# pad.net
KiCad netlist of a schematic drawn in EAGLE
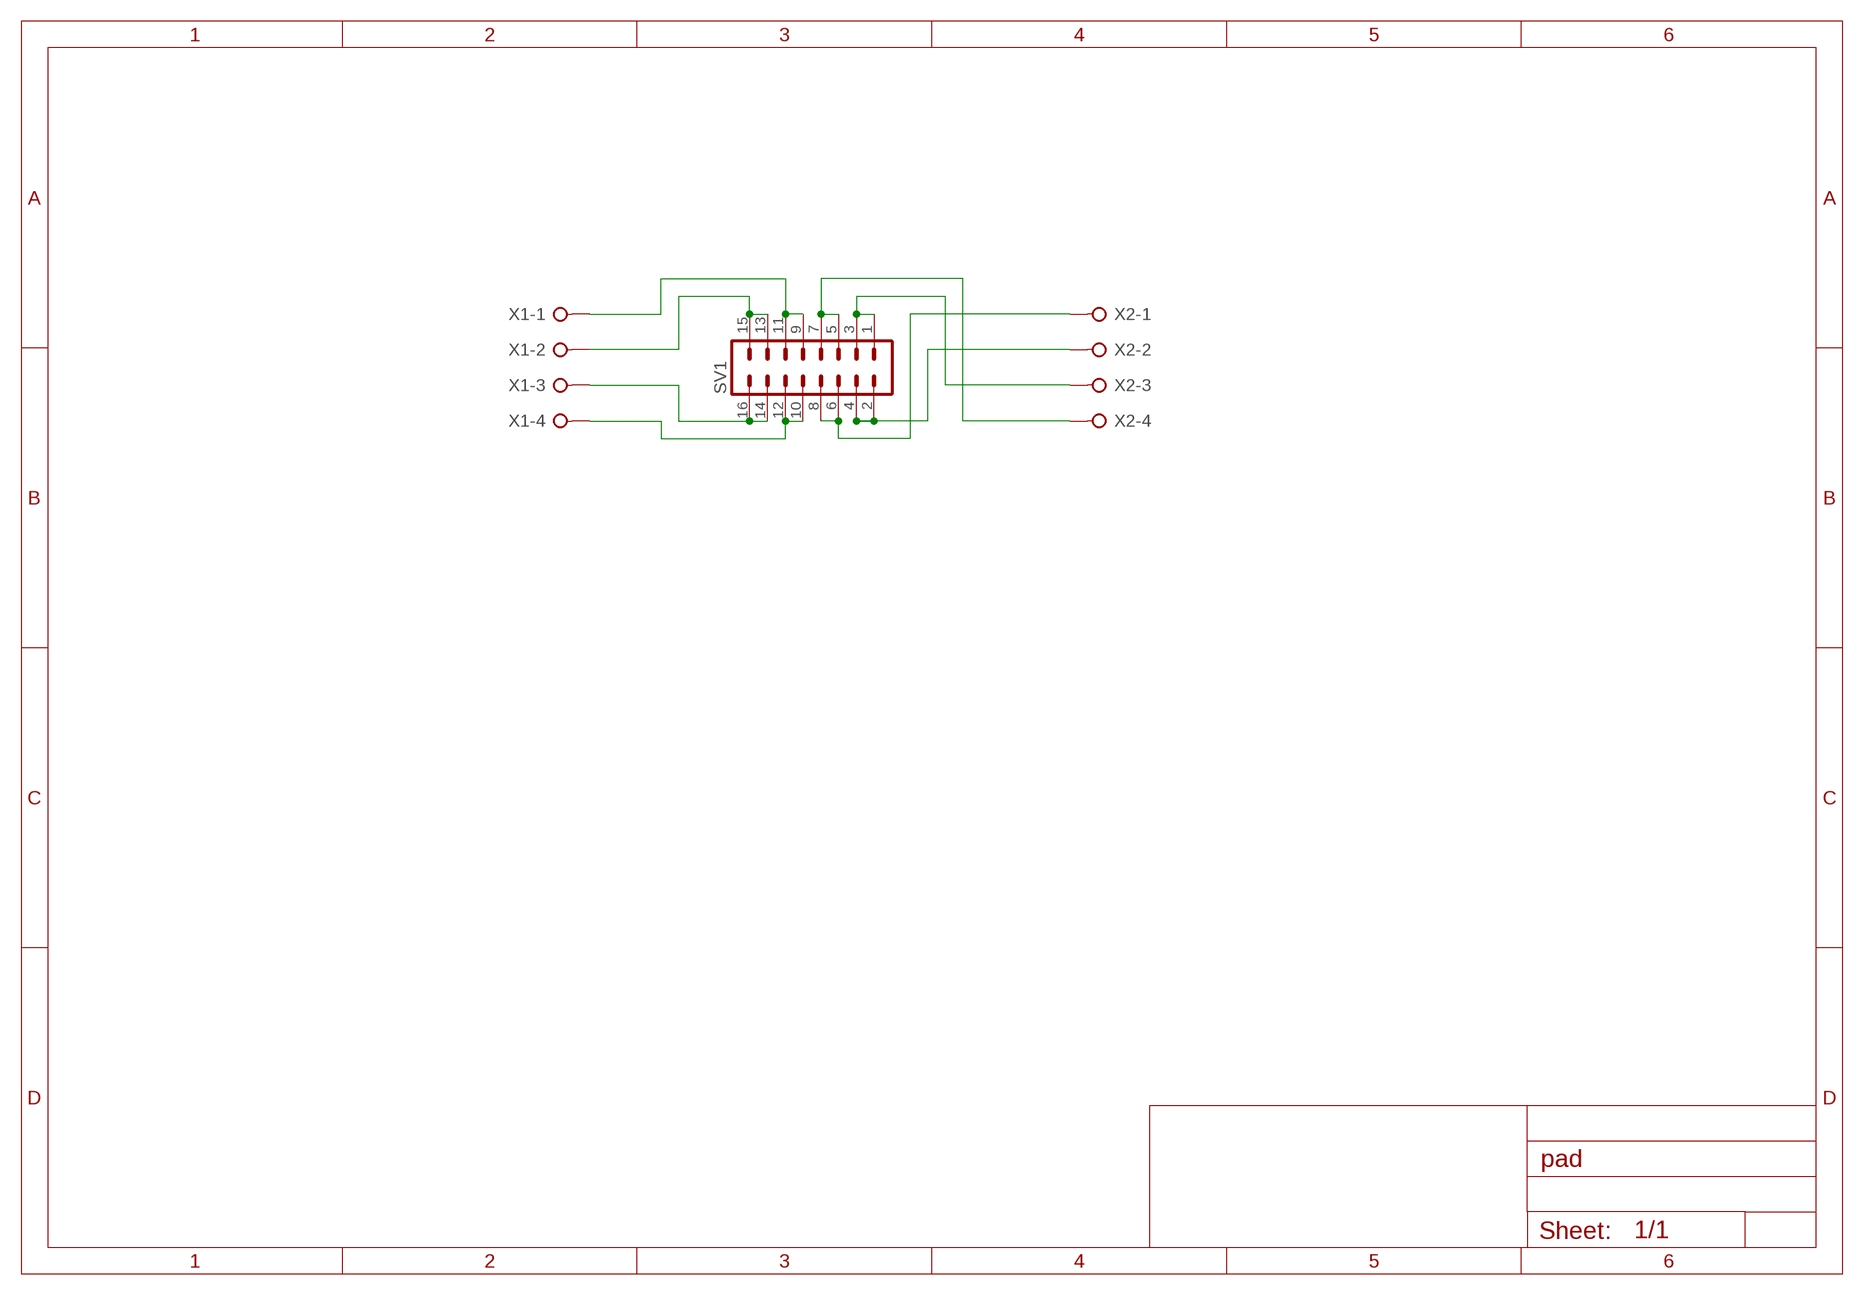
[diagram p0: schematic, sheet 1]

(export (version "E")
  (design (tool "Eeschema 10.0.6"))
  (components
    (comp (ref "SV1")
      (value "MA08-2")
      (footprint "eagle-import:MA08-2")
      (libsource (lib "eagle-import") (part "MA08-2"))
    )
    (comp (ref "X1")
      (value "W237-04P")
      (footprint "eagle-import:W237-4P")
      (libsource (lib "eagle-import") (part "W237-04P"))
    )
    (comp (ref "X2")
      (value "W237-04P")
      (footprint "eagle-import:W237-4P")
      (libsource (lib "eagle-import") (part "W237-04P"))
    )
  )
  (nets
    (net (code "1") (name "Net-(X1A-KL)") (class "Default")
      (node (ref "SV1") (pin "11") (pinfunction "11_11") (pintype "passive"))
      (node (ref "SV1") (pin "9") (pinfunction "9_9") (pintype "passive"))
      (node (ref "X1") (pin "1") (pinfunction "KL_1") (pintype "passive"))
    )
    (net (code "2") (name "Net-(X1B-KL)") (class "Default")
      (node (ref "SV1") (pin "13") (pinfunction "13_13") (pintype "passive"))
      (node (ref "SV1") (pin "15") (pinfunction "15_15") (pintype "passive"))
      (node (ref "X1") (pin "2") (pinfunction "KL_2") (pintype "passive"))
    )
    (net (code "3") (name "Net-(X1C-KL)") (class "Default")
      (node (ref "SV1") (pin "14") (pinfunction "14_14") (pintype "passive"))
      (node (ref "SV1") (pin "16") (pinfunction "16_16") (pintype "passive"))
      (node (ref "X1") (pin "3") (pinfunction "KL_3") (pintype "passive"))
    )
    (net (code "4") (name "Net-(X1D-KL)") (class "Default")
      (node (ref "SV1") (pin "10") (pinfunction "10_10") (pintype "passive"))
      (node (ref "SV1") (pin "12") (pinfunction "12_12") (pintype "passive"))
      (node (ref "X1") (pin "4") (pinfunction "KL_4") (pintype "passive"))
    )
    (net (code "5") (name "Net-(X2A-KL)") (class "Default")
      (node (ref "SV1") (pin "6") (pinfunction "6_6") (pintype "passive"))
      (node (ref "SV1") (pin "8") (pinfunction "8_8") (pintype "passive"))
      (node (ref "X2") (pin "1") (pinfunction "KL_1") (pintype "passive"))
    )
    (net (code "6") (name "Net-(X2B-KL)") (class "Default")
      (node (ref "SV1") (pin "2") (pinfunction "2_2") (pintype "passive"))
      (node (ref "SV1") (pin "4") (pinfunction "4_4") (pintype "passive"))
      (node (ref "X2") (pin "2") (pinfunction "KL_2") (pintype "passive"))
    )
    (net (code "7") (name "Net-(X2C-KL)") (class "Default")
      (node (ref "SV1") (pin "1") (pinfunction "1_1") (pintype "passive"))
      (node (ref "SV1") (pin "3") (pinfunction "3_3") (pintype "passive"))
      (node (ref "X2") (pin "3") (pinfunction "KL_3") (pintype "passive"))
    )
    (net (code "8") (name "Net-(X2D-KL)") (class "Default")
      (node (ref "SV1") (pin "5") (pinfunction "5_5") (pintype "passive"))
      (node (ref "SV1") (pin "7") (pinfunction "7_7") (pintype "passive"))
      (node (ref "X2") (pin "4") (pinfunction "KL_4") (pintype "passive"))
    )
  )
)
